# Differential_Opamp.net
KiCad netlist of a schematic drawn in Altium Designer
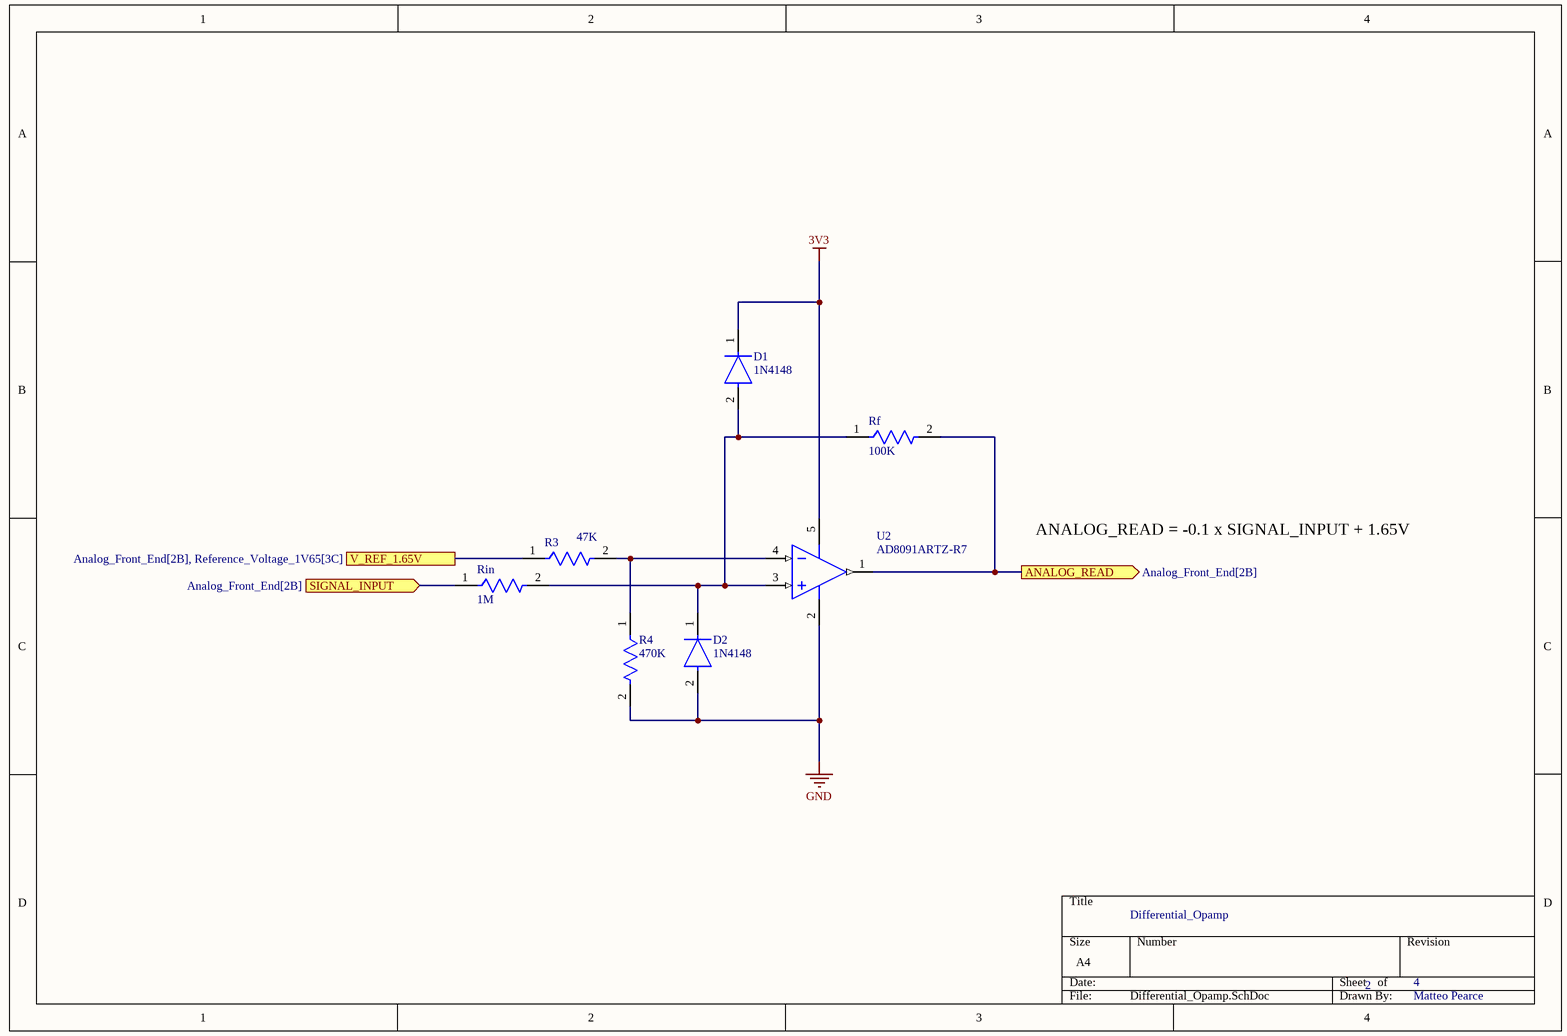
[diagram p0: Differential_Opamp.SchDoc]

(export (version "E")
  (design (tool "Eeschema 10.0.6"))
  (components
    (comp (ref "D1")
      (value "1N4148")
      (footprint "FP-017AG-MFG")
      (description "DIODE GEN PURP 100V 200MA DO35")
      (fields (field (name "VOLTAGE") "100V"))
      (libsource (lib "Altium Content Vault") (part "d7152d700b627762746794eb795d46e"))
    )
    (comp (ref "D2")
      (value "1N4148")
      (footprint "FP-017AG-MFG")
      (description "DIODE GEN PURP 100V 200MA DO35")
      (fields (field (name "VOLTAGE") "100V"))
      (libsource (lib "Altium Content Vault") (part "d7152d700b627762746794eb795d46e"))
    )
    (comp (ref "R3")
      (value "47K")
      (footprint "FP-CR1206-IPC_B")
      (description "Thick Film Chip Resistors 1206 47kΩ 0.25W 1% 100ppm/°C")
      (fields (field (name "TOLERANCE") "1%"))
      (libsource (lib "Altium Content Vault") (part "1029c3af85768c4190bb7ad29bc67b5"))
    )
    (comp (ref "R4")
      (value "470K")
      (footprint "FP-CR1206-IPC_C")
      (description "Thick Film Chip Resistors 1206 470kΩ 0.25W 1% 100ppm/°C")
      (fields (field (name "TOLERANCE") "1%"))
      (libsource (lib "Altium Content Vault") (part "1029c3af85768c4190bb7ad29bc67b5"))
    )
    (comp (ref "Rf")
      (value "100K")
      (footprint "FP-RP73P-1J-MFG")
      (description "RP73P 0603 100KΩ 0.166W 25ppm/°C 0.10% 100V")
      (fields (field (name "MANUFACTURER PART NUMBER") "RP73PF1J100KBTDF"))
      (libsource (lib "Altium Content Vault") (part "1029c3af85768c4190bb7ad29bc67b5"))
    )
    (comp (ref "Rin")
      (value "1M")
      (footprint "FP-MCR01-IPC_B")
      (description "Thick Film Chip Resistor, 0402, 1MΩ, 0.5%, 50ppm/°C, 0.063W, 50V")
      (libsource (lib "Altium Content Vault") (part "1029c3af85768c4190bb7ad29bc67b5"))
    )
    (comp (ref "U2")
      (value "AD8091ARTZ-R7")
      (footprint "ADI-RJ-5_M")
      (fields (field (name "MANUFACTURER") "Analog Devices") (field (name "GENERIC PART NUMBER") "AD8091"))
      (libsource (lib "Altium Content Vault") (part "ADI-AD80XX-5"))
    )
  )
  (nets
    (net (code "1") (name "/ANALOG_READ") (class "Default")
      (node (ref "Rf") (pin "2") (pinfunction "2_2") (pintype "passive"))
      (node (ref "U2") (pin "1") (pinfunction "VOUT_1") (pintype "output"))
    )
    (net (code "2") (name "/SIGNAL_INPUT") (class "Default")
      (node (ref "Rin") (pin "1") (pinfunction "1_1") (pintype "passive"))
    )
    (net (code "3") (name "/V_REF_1.65V") (class "Default")
      (node (ref "R3") (pin "1") (pinfunction "1_1") (pintype "passive"))
    )
    (net (code "4") (name "3V3") (class "Default")
      (node (ref "D1") (pin "1") (pinfunction "C_1") (pintype "passive"))
      (node (ref "U2") (pin "5") (pinfunction "+VS_5") (pintype "power_in"))
    )
    (net (code "5") (name "GND") (class "Default")
      (node (ref "D2") (pin "2") (pinfunction "A_2") (pintype "passive"))
      (node (ref "R4") (pin "2") (pinfunction "2_2") (pintype "passive"))
      (node (ref "U2") (pin "2") (pinfunction "-VS_2") (pintype "power_in"))
    )
    (net (code "6") (name "Net-(D1-A)") (class "Default")
      (node (ref "D1") (pin "2") (pinfunction "A_2") (pintype "passive"))
      (node (ref "D2") (pin "1") (pinfunction "C_1") (pintype "passive"))
      (node (ref "Rf") (pin "1") (pinfunction "1_1") (pintype "passive"))
      (node (ref "Rin") (pin "2") (pinfunction "2_2") (pintype "passive"))
      (node (ref "U2") (pin "3") (pinfunction "+IN_3") (pintype "input"))
    )
    (net (code "7") (name "Net-(U2--IN)") (class "Default")
      (node (ref "R3") (pin "2") (pinfunction "2_2") (pintype "passive"))
      (node (ref "R4") (pin "1") (pinfunction "1_1") (pintype "passive"))
      (node (ref "U2") (pin "4") (pinfunction "-IN_4") (pintype "input"))
    )
  )
)
